# DS136-1_0.net
KiCad netlist of a schematic drawn in Altium Designer
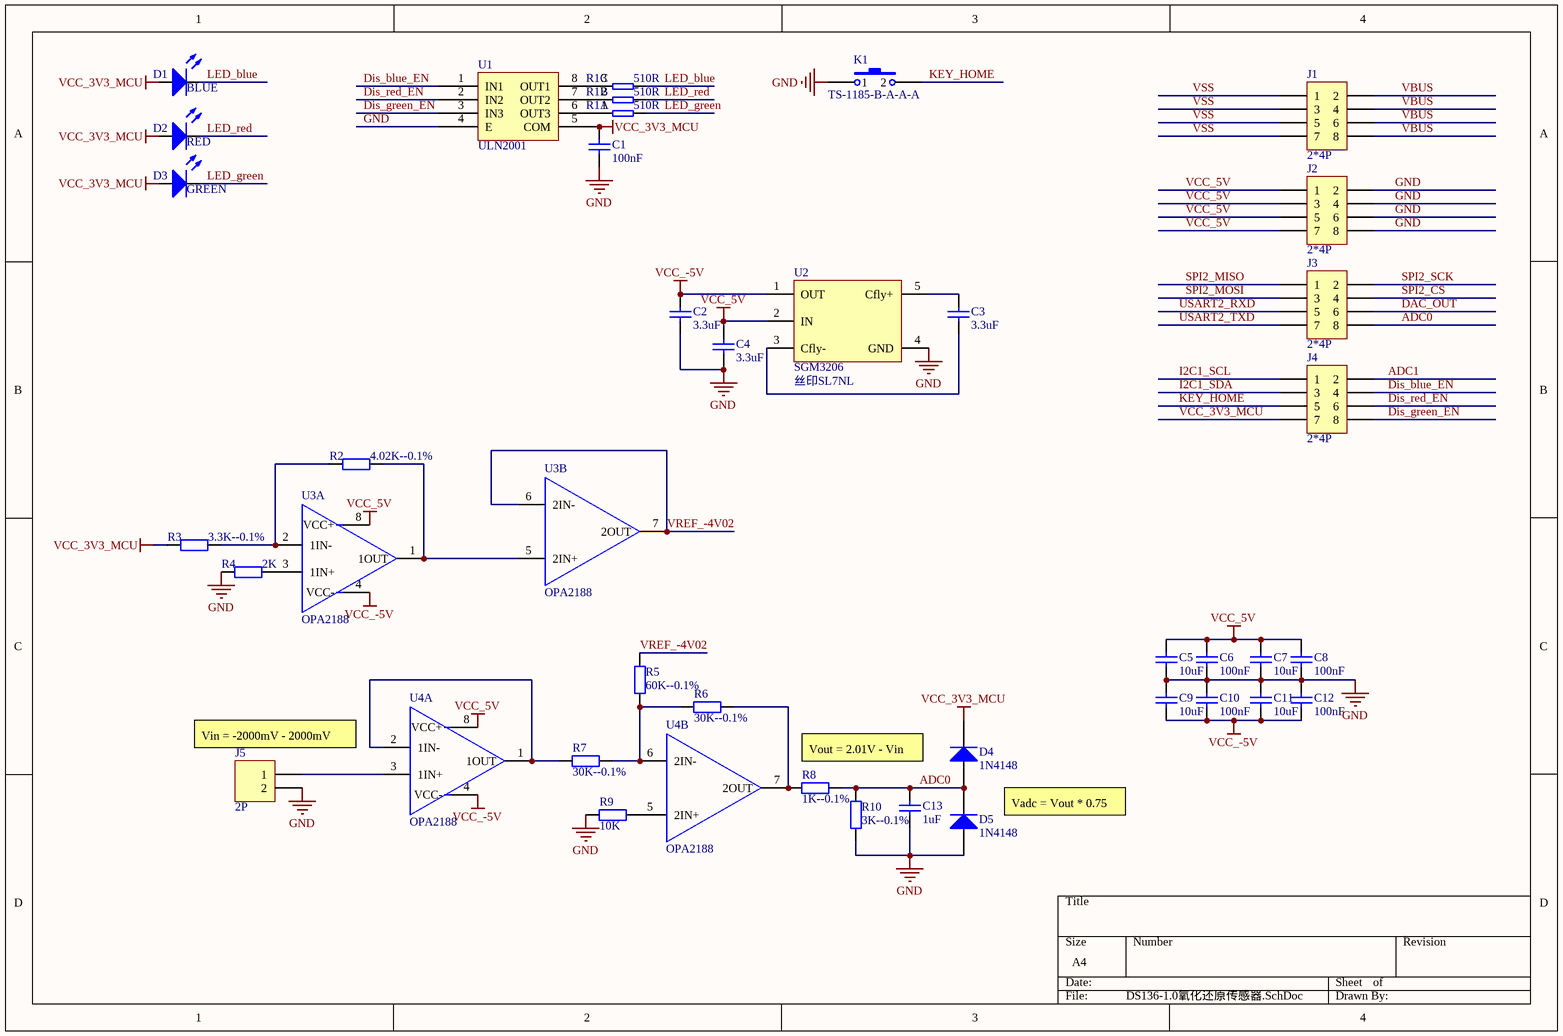
[diagram p0: DS136-1.0氧化还原传感器.SchDoc]

(export (version "E")
  (design (tool "Eeschema 10.0.6"))
  (components
    (comp (ref "C1")
      (value "100nF")
      (footprint "0603CAP")
      (description "贴片电容")
      (fields (field (name "Comment") "SMDCAP00013"))
      (libsource (lib "AD_SCH") (part "MLCC 100nF 50V ±10％ 0603"))
    )
    (comp (ref "C2")
      (value "3.3uF")
      (footprint "0603CAP")
      (description "贴片电容")
      (fields (field (name "Comment") "SMDCAP00013"))
      (libsource (lib "AD_SCH") (part "MLCC 100nF 50V ±10％ 0603"))
    )
    (comp (ref "C3")
      (value "3.3uF")
      (footprint "0603CAP")
      (description "贴片电容")
      (fields (field (name "Comment") "SMDCAP00013"))
      (libsource (lib "AD_SCH") (part "MLCC 100nF 50V ±10％ 0603"))
    )
    (comp (ref "C4")
      (value "3.3uF")
      (footprint "0603CAP")
      (description "贴片电容")
      (fields (field (name "Comment") "SMDCAP00013"))
      (libsource (lib "AD_SCH") (part "MLCC 100nF 50V ±10％ 0603"))
    )
    (comp (ref "C5")
      (value "10uF")
      (footprint "0603CAP")
      (description "贴片电容")
      (fields (field (name "Comment") "SMDCAP00016"))
      (libsource (lib "AD_SCH") (part "MLCC 10uF 50V ±10％ 0603"))
    )
    (comp (ref "C6")
      (value "100nF")
      (footprint "0603CAP")
      (description "贴片电容")
      (fields (field (name "Comment") "SMDCAP00013"))
      (libsource (lib "AD_SCH") (part "MLCC 100nF 50V ±10％ 0603"))
    )
    (comp (ref "C7")
      (value "10uF")
      (footprint "0603CAP")
      (description "贴片电容")
      (fields (field (name "Comment") "SMDCAP00016"))
      (libsource (lib "AD_SCH") (part "MLCC 10uF 50V ±10％ 0603"))
    )
    (comp (ref "C8")
      (value "100nF")
      (footprint "0603CAP")
      (description "贴片电容")
      (fields (field (name "Comment") "SMDCAP00013"))
      (libsource (lib "AD_SCH") (part "MLCC 100nF 50V ±10％ 0603"))
    )
    (comp (ref "C9")
      (value "10uF")
      (footprint "0603CAP")
      (description "贴片电容")
      (fields (field (name "Comment") "SMDCAP00016"))
      (libsource (lib "AD_SCH") (part "MLCC 10uF 50V ±10％ 0603"))
    )
    (comp (ref "C10")
      (value "100nF")
      (footprint "0603CAP")
      (description "贴片电容")
      (fields (field (name "Comment") "SMDCAP00013"))
      (libsource (lib "AD_SCH") (part "MLCC 100nF 50V ±10％ 0603"))
    )
    (comp (ref "C11")
      (value "10uF")
      (footprint "0603CAP")
      (description "贴片电容")
      (fields (field (name "Comment") "SMDCAP00016"))
      (libsource (lib "AD_SCH") (part "MLCC 10uF 50V ±10％ 0603"))
    )
    (comp (ref "C12")
      (value "100nF")
      (footprint "0603CAP")
      (description "贴片电容")
      (fields (field (name "Comment") "SMDCAP00013"))
      (libsource (lib "AD_SCH") (part "MLCC 100nF 50V ±10％ 0603"))
    )
    (comp (ref "C13")
      (value "1uF")
      (footprint "0603CAP")
      (description "贴片电容")
      (fields (field (name "Comment") "SMDCAP00015"))
      (libsource (lib "AD_SCH") (part "MLCC 1uF 50V ±10％ 0603"))
    )
    (comp (ref "D1")
      (value "BLUE")
      (footprint "LED_0805")
      (description "贴片LED")
      (fields (field (name "Comment") "SMDLED00010"))
      (libsource (lib "AD_SCH") (part "Chip 蓝色LED 0805"))
    )
    (comp (ref "D2")
      (value "RED")
      (footprint "LED_0805")
      (description "贴片LED")
      (fields (field (name "Comment") "SMDLED00003"))
      (libsource (lib "AD_SCH") (part "Chip 红色LED 0805"))
    )
    (comp (ref "D3")
      (value "GREEN")
      (footprint "LED_0805")
      (description "贴片LED")
      (fields (field (name "Comment") "Chip 翠绿LED 0805"))
      (libsource (lib "AD_SCH") (part "Chip 翠绿LED 0805"))
    )
    (comp (ref "D4")
      (value "1N4148")
      (footprint "LL-34")
      (description "贴片二极管")
      (fields (field (name "Comment") "SMDDIODE02001"))
      (libsource (lib "AD_SCH") (part "玻封 1/2W 1N4148 LL-34"))
    )
    (comp (ref "D5")
      (value "1N4148")
      (footprint "LL-34")
      (description "贴片二极管")
      (fields (field (name "Comment") "SMDDIODE02001"))
      (libsource (lib "AD_SCH") (part "玻封 1/2W 1N4148 LL-34"))
    )
    (comp (ref "J1")
      (value "2*4P")
      (footprint "X1321WVS-2x04J-C40D53")
      (description "双排针2x4P 立贴 1.27mm")
      (fields (field (name "Comment") "X1321WVS-2x04J-C40D53"))
      (libsource (lib "AD_SCH") (part "X1321WVS-2x04J-C40D53"))
    )
    (comp (ref "J2")
      (value "2*4P")
      (footprint "X1321WVS-2x04J-C40D53")
      (description "双排针2x4P 立贴 1.27mm")
      (fields (field (name "Comment") "X1321WVS-2x04J-C40D53"))
      (libsource (lib "AD_SCH") (part "X1321WVS-2x04J-C40D53"))
    )
    (comp (ref "J3")
      (value "2*4P")
      (footprint "X1321WVS-2x04J-C40D53")
      (description "双排针2x4P 立贴 1.27mm")
      (fields (field (name "Comment") "X1321WVS-2x04J-C40D53"))
      (libsource (lib "AD_SCH") (part "X1321WVS-2x04J-C40D53"))
    )
    (comp (ref "J4")
      (value "2*4P")
      (footprint "X1321WVS-2x04J-C40D53")
      (description "双排针2x4P 立贴 1.27mm")
      (fields (field (name "Comment") "X1321WVS-2x04J-C40D53"))
      (libsource (lib "AD_SCH") (part "X1321WVS-2x04J-C40D53"))
    )
    (comp (ref "J5")
      (value "2P")
      (footprint "SIP2")
      (description "单排直针")
      (fields (field (name "Comment") "SL000000042"))
      (libsource (lib "AD_SCH") (part "DIP2 单排直针 1*40P 间距2.54mm 针长11mm 铜"))
    )
    (comp (ref "K1")
      (value "TS-1185-B-A-A-A")
      (footprint "KEY_TS-1185-x-A-A-A")
      (description "轻触开关")
      (libsource (lib "AD_SCH") (part "TS-1185-B-A-A-A"))
    )
    (comp (ref "R1")
      (value "510R")
      (footprint "0603RES_Pack4")
      (description "贴片排阻")
      (fields (field (name "Comment") "SMDRES05003"))
      (libsource (lib "AD_SCH") (part "Chip R*4 510R 1/16W ±5％ 0603"))
    )
    (comp (ref "R2")
      (value "4.02K--0.1%")
      (footprint "0603RES")
      (description "贴片电阻")
      (fields (field (name "Comment") "SMDRES00060"))
      (libsource (lib "AD_SCH") (part "Chip 30K 1/16W ±1％ 0603"))
    )
    (comp (ref "R3")
      (value "3.3K--0.1%")
      (footprint "0603RES")
      (description "贴片电阻")
      (fields (field (name "Comment") "SMDRES00090"))
      (libsource (lib "AD_SCH") (part "Chip 3.3K 1/16W ±1％ 0603"))
    )
    (comp (ref "R4")
      (value "2K")
      (footprint "0603RES")
      (description "贴片电阻")
      (fields (field (name "Comment") "SMDRES00042"))
      (libsource (lib "AD_SCH") (part "Chip 2K 1/16W ±1％ 0603"))
    )
    (comp (ref "R5")
      (value "60K--0.1%")
      (footprint "0603RES")
      (description "贴片电阻")
      (fields (field (name "Comment") "SMDRES00060"))
      (libsource (lib "") (part "Chip 30K 1/16W ±1％ 0603_1"))
    )
    (comp (ref "R6")
      (value "30K--0.1%")
      (footprint "0603RES")
      (description "贴片电阻")
      (fields (field (name "Comment") "SMDRES00060"))
      (libsource (lib "") (part "Chip 30K 1/16W ±1％ 0603_2"))
    )
    (comp (ref "R7")
      (value "30K--0.1%")
      (footprint "0603RES")
      (description "贴片电阻")
      (fields (field (name "Comment") "SMDRES00060"))
      (libsource (lib "") (part "Chip 30K 1/16W ±1％ 0603_2"))
    )
    (comp (ref "R8")
      (value "1K--0.1%")
      (footprint "0603RES")
      (description "贴片电阻")
      (fields (field (name "Comment") "SMDRES00034"))
      (libsource (lib "AD_SCH") (part "Chip 1K 1/16W ±1％ 0603"))
    )
    (comp (ref "R9")
      (value "10K")
      (footprint "0603RES")
      (description "贴片电阻")
      (fields (field (name "Comment") "SMDRES00056"))
      (libsource (lib "AD_SCH") (part "Chip 10K 1/16W ±1％ 0603"))
    )
    (comp (ref "R10")
      (value "3K--0.1%")
      (footprint "0603RES")
      (description "贴片电阻")
      (fields (field (name "Comment") "Chip 3K 1/16W ±1％ 0603"))
      (libsource (lib "AD_SCH") (part "Chip 3K 1/16W ±1％ 0603"))
    )
    (comp (ref "U1")
      (value "ULN2001")
      (footprint "SO-8")
      (description "电机驱动芯片")
      (fields (field (name "Comment") "SMDIC000018"))
      (libsource (lib "AD_SCH") (part "ULN2001 SOP-8"))
    )
    (comp (ref "U2")
      (value "SGM3206")
      (footprint "SOT23-5")
      (description "电荷泵芯片")
      (fields (field (name "ALTIUM_VALUE") "丝印SL7NL"))
      (libsource (lib "AD_SCH") (part "SGM3206"))
    )
    (comp (ref "U3") (value "OPA2188") (footprint "SO-8") (libsource (lib "AD_SCH") (part "TL062C")))
    (comp (ref "U4") (value "OPA2188") (footprint "SO-8") (libsource (lib "AD_SCH") (part "TL062C")))
  )
  (nets
    (net (code "1") (name "/ADC0") (class "Default")
      (node (ref "C13") (pin "2") (pinfunction "2_2") (pintype "passive"))
      (node (ref "D4") (pin "1") (pinfunction "A_1") (pintype "passive"))
      (node (ref "D5") (pin "2") (pinfunction "K_2") (pintype "passive"))
      (node (ref "J3") (pin "8") (pinfunction "8_8") (pintype "passive"))
      (node (ref "R10") (pin "2") (pinfunction "2_2") (pintype "passive"))
      (node (ref "R8") (pin "2") (pinfunction "2_2") (pintype "passive"))
    )
    (net (code "2") (name "/ADC1") (class "Default")
      (node (ref "J4") (pin "2") (pinfunction "2_2") (pintype "passive"))
    )
    (net (code "3") (name "/DAC_OUT") (class "Default")
      (node (ref "J3") (pin "6") (pinfunction "6_6") (pintype "passive"))
    )
    (net (code "4") (name "/Dis_blue_EN") (class "Default")
      (node (ref "J4") (pin "4") (pinfunction "4_4") (pintype "passive"))
      (node (ref "U1") (pin "1") (pinfunction "IN1_1") (pintype "passive"))
    )
    (net (code "5") (name "/Dis_green_EN") (class "Default")
      (node (ref "J4") (pin "8") (pinfunction "8_8") (pintype "passive"))
      (node (ref "U1") (pin "3") (pinfunction "IN3_3") (pintype "passive"))
    )
    (net (code "6") (name "/Dis_red_EN") (class "Default")
      (node (ref "J4") (pin "6") (pinfunction "6_6") (pintype "passive"))
      (node (ref "U1") (pin "2") (pinfunction "IN2_2") (pintype "passive"))
    )
    (net (code "7") (name "/I2C1_SCL") (class "Default")
      (node (ref "J4") (pin "1") (pinfunction "1_1") (pintype "passive"))
    )
    (net (code "8") (name "/I2C1_SDA") (class "Default")
      (node (ref "J4") (pin "3") (pinfunction "3_3") (pintype "passive"))
    )
    (net (code "9") (name "/KEY_HOME") (class "Default")
      (node (ref "J4") (pin "5") (pinfunction "5_5") (pintype "passive"))
      (node (ref "K1") (pin "2") (pinfunction "2_2") (pintype "passive"))
    )
    (net (code "10") (name "/LED_blue") (class "Default")
      (node (ref "D1") (pin "2") (pinfunction "K_2") (pintype "passive"))
      (node (ref "R1") (pin "6") (pinfunction "6_6") (pintype "passive"))
    )
    (net (code "11") (name "/LED_green") (class "Default")
      (node (ref "D3") (pin "2") (pinfunction "K_2") (pintype "passive"))
      (node (ref "R1") (pin "8") (pinfunction "8_8") (pintype "passive"))
    )
    (net (code "12") (name "/LED_red") (class "Default")
      (node (ref "D2") (pin "2") (pinfunction "K_2") (pintype "passive"))
      (node (ref "R1") (pin "7") (pinfunction "7_7") (pintype "passive"))
    )
    (net (code "13") (name "/SPI2_CS") (class "Default")
      (node (ref "J3") (pin "4") (pinfunction "4_4") (pintype "passive"))
    )
    (net (code "14") (name "/SPI2_MISO") (class "Default")
      (node (ref "J3") (pin "1") (pinfunction "1_1") (pintype "passive"))
    )
    (net (code "15") (name "/SPI2_MOSI") (class "Default")
      (node (ref "J3") (pin "3") (pinfunction "3_3") (pintype "passive"))
    )
    (net (code "16") (name "/SPI2_SCK") (class "Default")
      (node (ref "J3") (pin "2") (pinfunction "2_2") (pintype "passive"))
    )
    (net (code "17") (name "/USART2_RXD") (class "Default")
      (node (ref "J3") (pin "5") (pinfunction "5_5") (pintype "passive"))
    )
    (net (code "18") (name "/USART2_TXD") (class "Default")
      (node (ref "J3") (pin "7") (pinfunction "7_7") (pintype "passive"))
    )
    (net (code "19") (name "/VBUS") (class "Default")
      (node (ref "J1") (pin "2") (pinfunction "2_2") (pintype "passive"))
      (node (ref "J1") (pin "4") (pinfunction "4_4") (pintype "passive"))
      (node (ref "J1") (pin "6") (pinfunction "6_6") (pintype "passive"))
      (node (ref "J1") (pin "8") (pinfunction "8_8") (pintype "passive"))
    )
    (net (code "20") (name "/VREF_-4V02") (class "Default")
      (node (ref "R5") (pin "2") (pinfunction "2_2") (pintype "passive"))
      (node (ref "U3") (pin "6") (pinfunction "2IN-_6") (pintype "passive"))
      (node (ref "U3") (pin "7") (pinfunction "2OUT_7") (pintype "passive"))
    )
    (net (code "21") (name "/VSS") (class "Default")
      (node (ref "J1") (pin "1") (pinfunction "1_1") (pintype "passive"))
      (node (ref "J1") (pin "3") (pinfunction "3_3") (pintype "passive"))
      (node (ref "J1") (pin "5") (pinfunction "5_5") (pintype "passive"))
      (node (ref "J1") (pin "7") (pinfunction "7_7") (pintype "passive"))
    )
    (net (code "22") (name "GND") (class "Default")
      (node (ref "C1") (pin "1") (pinfunction "1_1") (pintype "passive"))
      (node (ref "C10") (pin "2") (pinfunction "2_2") (pintype "passive"))
      (node (ref "C11") (pin "2") (pinfunction "2_2") (pintype "passive"))
      (node (ref "C12") (pin "2") (pinfunction "2_2") (pintype "passive"))
      (node (ref "C13") (pin "1") (pinfunction "1_1") (pintype "passive"))
      (node (ref "C2") (pin "1") (pinfunction "1_1") (pintype "passive"))
      (node (ref "C4") (pin "2") (pinfunction "2_2") (pintype "passive"))
      (node (ref "C5") (pin "1") (pinfunction "1_1") (pintype "passive"))
      (node (ref "C6") (pin "1") (pinfunction "1_1") (pintype "passive"))
      (node (ref "C7") (pin "1") (pinfunction "1_1") (pintype "passive"))
      (node (ref "C8") (pin "1") (pinfunction "1_1") (pintype "passive"))
      (node (ref "C9") (pin "2") (pinfunction "2_2") (pintype "passive"))
      (node (ref "D5") (pin "1") (pinfunction "A_1") (pintype "passive"))
      (node (ref "J2") (pin "2") (pinfunction "2_2") (pintype "passive"))
      (node (ref "J2") (pin "4") (pinfunction "4_4") (pintype "passive"))
      (node (ref "J2") (pin "6") (pinfunction "6_6") (pintype "passive"))
      (node (ref "J2") (pin "8") (pinfunction "8_8") (pintype "passive"))
      (node (ref "J5") (pin "2") (pinfunction "2_2") (pintype "passive"))
      (node (ref "K1") (pin "1") (pinfunction "1_1") (pintype "passive"))
      (node (ref "R10") (pin "1") (pinfunction "1_1") (pintype "passive"))
      (node (ref "R4") (pin "1") (pinfunction "1_1") (pintype "passive"))
      (node (ref "R9") (pin "1") (pinfunction "1_1") (pintype "passive"))
      (node (ref "U1") (pin "4") (pinfunction "E_4") (pintype "passive"))
      (node (ref "U2") (pin "4") (pinfunction "GND_4") (pintype "passive"))
    )
    (net (code "23") (name "Net-(U1-OUT1)") (class "Default")
      (node (ref "R1") (pin "3") (pinfunction "3_3") (pintype "passive"))
      (node (ref "U1") (pin "8") (pinfunction "OUT1_8") (pintype "passive"))
    )
    (net (code "24") (name "Net-(U1-OUT2)") (class "Default")
      (node (ref "R1") (pin "2") (pinfunction "2_2") (pintype "passive"))
      (node (ref "U1") (pin "7") (pinfunction "OUT2_7") (pintype "passive"))
    )
    (net (code "25") (name "Net-(U1-OUT3)") (class "Default")
      (node (ref "R1") (pin "1") (pinfunction "1_1") (pintype "passive"))
      (node (ref "U1") (pin "6") (pinfunction "OUT3_6") (pintype "passive"))
    )
    (net (code "26") (name "Net-(U2-Cfly+)") (class "Default")
      (node (ref "C3") (pin "1") (pinfunction "1_1") (pintype "passive"))
      (node (ref "U2") (pin "5") (pinfunction "Cfly+_5") (pintype "passive"))
    )
    (net (code "27") (name "Net-(U2-Cfly-)") (class "Default")
      (node (ref "C3") (pin "2") (pinfunction "2_2") (pintype "passive"))
      (node (ref "U2") (pin "3") (pinfunction "Cfly-_3") (pintype "passive"))
    )
    (net (code "28") (name "Net-(U3A-1IN+)") (class "Default")
      (node (ref "R4") (pin "2") (pinfunction "2_2") (pintype "passive"))
      (node (ref "U3") (pin "3") (pinfunction "1IN+_3") (pintype "passive"))
    )
    (net (code "29") (name "Net-(U3A-1IN-)") (class "Default")
      (node (ref "R2") (pin "2") (pinfunction "2_2") (pintype "passive"))
      (node (ref "R3") (pin "1") (pinfunction "1_1") (pintype "passive"))
      (node (ref "U3") (pin "2") (pinfunction "1IN-_2") (pintype "passive"))
    )
    (net (code "30") (name "Net-(U3A-1OUT)") (class "Default")
      (node (ref "R2") (pin "1") (pinfunction "1_1") (pintype "passive"))
      (node (ref "U3") (pin "1") (pinfunction "1OUT_1") (pintype "passive"))
      (node (ref "U3") (pin "5") (pinfunction "2IN+_5") (pintype "passive"))
    )
    (net (code "31") (name "Net-(U4A-1IN+)") (class "Default")
      (node (ref "J5") (pin "1") (pinfunction "1_1") (pintype "passive"))
      (node (ref "U4") (pin "3") (pinfunction "1IN+_3") (pintype "passive"))
    )
    (net (code "32") (name "Net-(U4A-1IN-)") (class "Default")
      (node (ref "R7") (pin "1") (pinfunction "1_1") (pintype "passive"))
      (node (ref "U4") (pin "1") (pinfunction "1OUT_1") (pintype "passive"))
      (node (ref "U4") (pin "2") (pinfunction "1IN-_2") (pintype "passive"))
    )
    (net (code "33") (name "Net-(U4B-2IN+)") (class "Default")
      (node (ref "R9") (pin "2") (pinfunction "2_2") (pintype "passive"))
      (node (ref "U4") (pin "5") (pinfunction "2IN+_5") (pintype "passive"))
    )
    (net (code "34") (name "Net-(U4B-2IN-)") (class "Default")
      (node (ref "R5") (pin "1") (pinfunction "1_1") (pintype "passive"))
      (node (ref "R6") (pin "1") (pinfunction "1_1") (pintype "passive"))
      (node (ref "R7") (pin "2") (pinfunction "2_2") (pintype "passive"))
      (node (ref "U4") (pin "6") (pinfunction "2IN-_6") (pintype "passive"))
    )
    (net (code "35") (name "Net-(U4B-2OUT)") (class "Default")
      (node (ref "R6") (pin "2") (pinfunction "2_2") (pintype "passive"))
      (node (ref "R8") (pin "1") (pinfunction "1_1") (pintype "passive"))
      (node (ref "U4") (pin "7") (pinfunction "2OUT_7") (pintype "passive"))
    )
    (net (code "36") (name "VCC_-5V") (class "Default")
      (node (ref "C10") (pin "1") (pinfunction "1_1") (pintype "passive"))
      (node (ref "C11") (pin "1") (pinfunction "1_1") (pintype "passive"))
      (node (ref "C12") (pin "1") (pinfunction "1_1") (pintype "passive"))
      (node (ref "C2") (pin "2") (pinfunction "2_2") (pintype "passive"))
      (node (ref "C9") (pin "1") (pinfunction "1_1") (pintype "passive"))
      (node (ref "U2") (pin "1") (pinfunction "OUT_1") (pintype "passive"))
      (node (ref "U3") (pin "4") (pinfunction "VCC-_4") (pintype "passive"))
      (node (ref "U4") (pin "4") (pinfunction "VCC-_4") (pintype "passive"))
    )
    (net (code "37") (name "VCC_3V3_MCU") (class "Default")
      (node (ref "C1") (pin "2") (pinfunction "2_2") (pintype "passive"))
      (node (ref "D1") (pin "1") (pinfunction "A_1") (pintype "passive"))
      (node (ref "D2") (pin "1") (pinfunction "A_1") (pintype "passive"))
      (node (ref "D3") (pin "1") (pinfunction "A_1") (pintype "passive"))
      (node (ref "D4") (pin "2") (pinfunction "K_2") (pintype "passive"))
      (node (ref "J4") (pin "7") (pinfunction "7_7") (pintype "passive"))
      (node (ref "R3") (pin "2") (pinfunction "2_2") (pintype "passive"))
      (node (ref "U1") (pin "5") (pinfunction "COM_5") (pintype "passive"))
    )
    (net (code "38") (name "VCC_5V") (class "Default")
      (node (ref "C4") (pin "1") (pinfunction "1_1") (pintype "passive"))
      (node (ref "C5") (pin "2") (pinfunction "2_2") (pintype "passive"))
      (node (ref "C6") (pin "2") (pinfunction "2_2") (pintype "passive"))
      (node (ref "C7") (pin "2") (pinfunction "2_2") (pintype "passive"))
      (node (ref "C8") (pin "2") (pinfunction "2_2") (pintype "passive"))
      (node (ref "J2") (pin "1") (pinfunction "1_1") (pintype "passive"))
      (node (ref "J2") (pin "3") (pinfunction "3_3") (pintype "passive"))
      (node (ref "J2") (pin "5") (pinfunction "5_5") (pintype "passive"))
      (node (ref "J2") (pin "7") (pinfunction "7_7") (pintype "passive"))
      (node (ref "U2") (pin "2") (pinfunction "IN_2") (pintype "passive"))
      (node (ref "U3") (pin "8") (pinfunction "VCC+_8") (pintype "passive"))
      (node (ref "U4") (pin "8") (pinfunction "VCC+_8") (pintype "passive"))
    )
  )
)
